# Controller_Board_Interface.net
KiCad netlist of a schematic drawn in Altium Designer
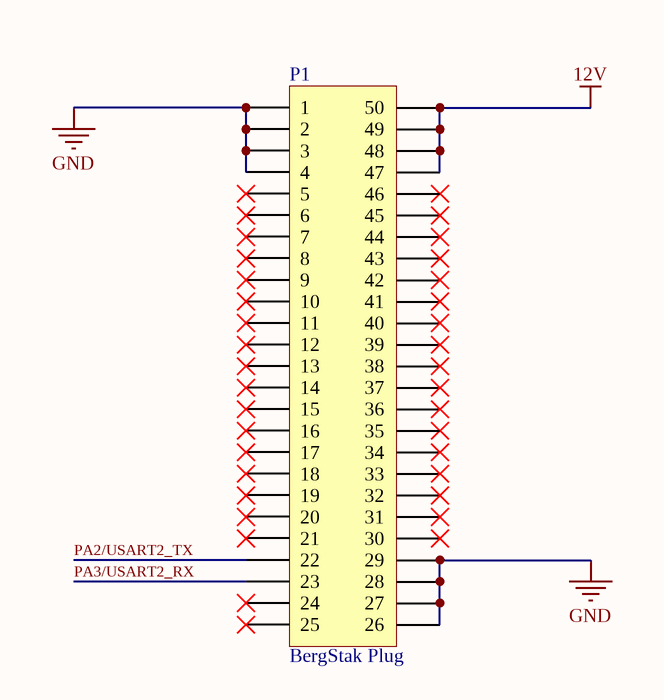
[diagram p0: Controller_Board_Interface.SchDoc]

(export (version "E")
  (design (tool "Eeschema 10.0.6"))
  (components
    (comp (ref "P1")
      (value "CONN 50POS Bergstak Plug 0.02\"")
      (footprint "CONN, Bergstak 50 Pos Plug")
      (description "50 Position Connector Plug, Outer Shroud Contacts Surface Mount Gold")
      (fields (field (name "SERIES") "BergStak Plug"))
      (libsource (lib "Schematic Diagrams") (part "CONN 50POS Bergstak Plug 0.02{dblquote}"))
    )
  )
  (nets
    (net (code "1") (name "/PA2{slash}USART2_TX") (class "Default")
      (node (ref "P1") (pin "22") (pinfunction "22_22") (pintype "passive"))
    )
    (net (code "2") (name "/PA3{slash}USART2_RX") (class "Default")
      (node (ref "P1") (pin "23") (pinfunction "23_23") (pintype "passive"))
    )
    (net (code "3") (name "12V") (class "Default")
      (node (ref "P1") (pin "47") (pinfunction "47_47") (pintype "passive"))
      (node (ref "P1") (pin "48") (pinfunction "48_48") (pintype "passive"))
      (node (ref "P1") (pin "49") (pinfunction "49_49") (pintype "passive"))
      (node (ref "P1") (pin "50") (pinfunction "50_50") (pintype "passive"))
    )
    (net (code "4") (name "GND") (class "Default")
      (node (ref "P1") (pin "1") (pinfunction "1_1") (pintype "passive"))
      (node (ref "P1") (pin "2") (pinfunction "2_2") (pintype "passive"))
      (node (ref "P1") (pin "26") (pinfunction "26_26") (pintype "passive"))
      (node (ref "P1") (pin "27") (pinfunction "27_27") (pintype "passive"))
      (node (ref "P1") (pin "28") (pinfunction "28_28") (pintype "passive"))
      (node (ref "P1") (pin "29") (pinfunction "29_29") (pintype "passive"))
      (node (ref "P1") (pin "3") (pinfunction "3_3") (pintype "passive"))
      (node (ref "P1") (pin "4") (pinfunction "4_4") (pintype "passive"))
    )
    (net (code "5") (name "unconnected-(P1-Pad5)") (class "Default")
      (node (ref "P1") (pin "5") (pinfunction "5_5") (pintype "passive+no_connect"))
    )
    (net (code "6") (name "unconnected-(P1-Pad6)") (class "Default")
      (node (ref "P1") (pin "6") (pinfunction "6_6") (pintype "passive+no_connect"))
    )
    (net (code "7") (name "unconnected-(P1-Pad7)") (class "Default")
      (node (ref "P1") (pin "7") (pinfunction "7_7") (pintype "passive+no_connect"))
    )
    (net (code "8") (name "unconnected-(P1-Pad8)") (class "Default")
      (node (ref "P1") (pin "8") (pinfunction "8_8") (pintype "passive+no_connect"))
    )
    (net (code "9") (name "unconnected-(P1-Pad9)") (class "Default")
      (node (ref "P1") (pin "9") (pinfunction "9_9") (pintype "passive+no_connect"))
    )
    (net (code "10") (name "unconnected-(P1-Pad10)") (class "Default")
      (node (ref "P1") (pin "10") (pinfunction "10_10") (pintype "passive+no_connect"))
    )
    (net (code "11") (name "unconnected-(P1-Pad11)") (class "Default")
      (node (ref "P1") (pin "11") (pinfunction "11_11") (pintype "passive+no_connect"))
    )
    (net (code "12") (name "unconnected-(P1-Pad12)") (class "Default")
      (node (ref "P1") (pin "12") (pinfunction "12_12") (pintype "passive+no_connect"))
    )
    (net (code "13") (name "unconnected-(P1-Pad13)") (class "Default")
      (node (ref "P1") (pin "13") (pinfunction "13_13") (pintype "passive+no_connect"))
    )
    (net (code "14") (name "unconnected-(P1-Pad14)") (class "Default")
      (node (ref "P1") (pin "14") (pinfunction "14_14") (pintype "passive+no_connect"))
    )
    (net (code "15") (name "unconnected-(P1-Pad15)") (class "Default")
      (node (ref "P1") (pin "15") (pinfunction "15_15") (pintype "passive+no_connect"))
    )
    (net (code "16") (name "unconnected-(P1-Pad16)") (class "Default")
      (node (ref "P1") (pin "16") (pinfunction "16_16") (pintype "passive+no_connect"))
    )
    (net (code "17") (name "unconnected-(P1-Pad17)") (class "Default")
      (node (ref "P1") (pin "17") (pinfunction "17_17") (pintype "passive+no_connect"))
    )
    (net (code "18") (name "unconnected-(P1-Pad18)") (class "Default")
      (node (ref "P1") (pin "18") (pinfunction "18_18") (pintype "passive+no_connect"))
    )
    (net (code "19") (name "unconnected-(P1-Pad19)") (class "Default")
      (node (ref "P1") (pin "19") (pinfunction "19_19") (pintype "passive+no_connect"))
    )
    (net (code "20") (name "unconnected-(P1-Pad20)") (class "Default")
      (node (ref "P1") (pin "20") (pinfunction "20_20") (pintype "passive+no_connect"))
    )
    (net (code "21") (name "unconnected-(P1-Pad21)") (class "Default")
      (node (ref "P1") (pin "21") (pinfunction "21_21") (pintype "passive+no_connect"))
    )
    (net (code "22") (name "unconnected-(P1-Pad24)") (class "Default")
      (node (ref "P1") (pin "24") (pinfunction "24_24") (pintype "passive+no_connect"))
    )
    (net (code "23") (name "unconnected-(P1-Pad25)") (class "Default")
      (node (ref "P1") (pin "25") (pinfunction "25_25") (pintype "passive+no_connect"))
    )
    (net (code "24") (name "unconnected-(P1-Pad30)") (class "Default")
      (node (ref "P1") (pin "30") (pinfunction "30_30") (pintype "passive+no_connect"))
    )
    (net (code "25") (name "unconnected-(P1-Pad31)") (class "Default")
      (node (ref "P1") (pin "31") (pinfunction "31_31") (pintype "passive+no_connect"))
    )
    (net (code "26") (name "unconnected-(P1-Pad32)") (class "Default")
      (node (ref "P1") (pin "32") (pinfunction "32_32") (pintype "passive+no_connect"))
    )
    (net (code "27") (name "unconnected-(P1-Pad33)") (class "Default")
      (node (ref "P1") (pin "33") (pinfunction "33_33") (pintype "passive+no_connect"))
    )
    (net (code "28") (name "unconnected-(P1-Pad34)") (class "Default")
      (node (ref "P1") (pin "34") (pinfunction "34_34") (pintype "passive+no_connect"))
    )
    (net (code "29") (name "unconnected-(P1-Pad35)") (class "Default")
      (node (ref "P1") (pin "35") (pinfunction "35_35") (pintype "passive+no_connect"))
    )
    (net (code "30") (name "unconnected-(P1-Pad36)") (class "Default")
      (node (ref "P1") (pin "36") (pinfunction "36_36") (pintype "passive+no_connect"))
    )
    (net (code "31") (name "unconnected-(P1-Pad37)") (class "Default")
      (node (ref "P1") (pin "37") (pinfunction "37_37") (pintype "passive+no_connect"))
    )
    (net (code "32") (name "unconnected-(P1-Pad38)") (class "Default")
      (node (ref "P1") (pin "38") (pinfunction "38_38") (pintype "passive+no_connect"))
    )
    (net (code "33") (name "unconnected-(P1-Pad39)") (class "Default")
      (node (ref "P1") (pin "39") (pinfunction "39_39") (pintype "passive+no_connect"))
    )
    (net (code "34") (name "unconnected-(P1-Pad40)") (class "Default")
      (node (ref "P1") (pin "40") (pinfunction "40_40") (pintype "passive+no_connect"))
    )
    (net (code "35") (name "unconnected-(P1-Pad41)") (class "Default")
      (node (ref "P1") (pin "41") (pinfunction "41_41") (pintype "passive+no_connect"))
    )
    (net (code "36") (name "unconnected-(P1-Pad42)") (class "Default")
      (node (ref "P1") (pin "42") (pinfunction "42_42") (pintype "passive+no_connect"))
    )
    (net (code "37") (name "unconnected-(P1-Pad43)") (class "Default")
      (node (ref "P1") (pin "43") (pinfunction "43_43") (pintype "passive+no_connect"))
    )
    (net (code "38") (name "unconnected-(P1-Pad44)") (class "Default")
      (node (ref "P1") (pin "44") (pinfunction "44_44") (pintype "passive+no_connect"))
    )
    (net (code "39") (name "unconnected-(P1-Pad45)") (class "Default")
      (node (ref "P1") (pin "45") (pinfunction "45_45") (pintype "passive+no_connect"))
    )
    (net (code "40") (name "unconnected-(P1-Pad46)") (class "Default")
      (node (ref "P1") (pin "46") (pinfunction "46_46") (pintype "passive+no_connect"))
    )
  )
)
